# open-bldc.net
KiCad netlist of a schematic drawn in EAGLE
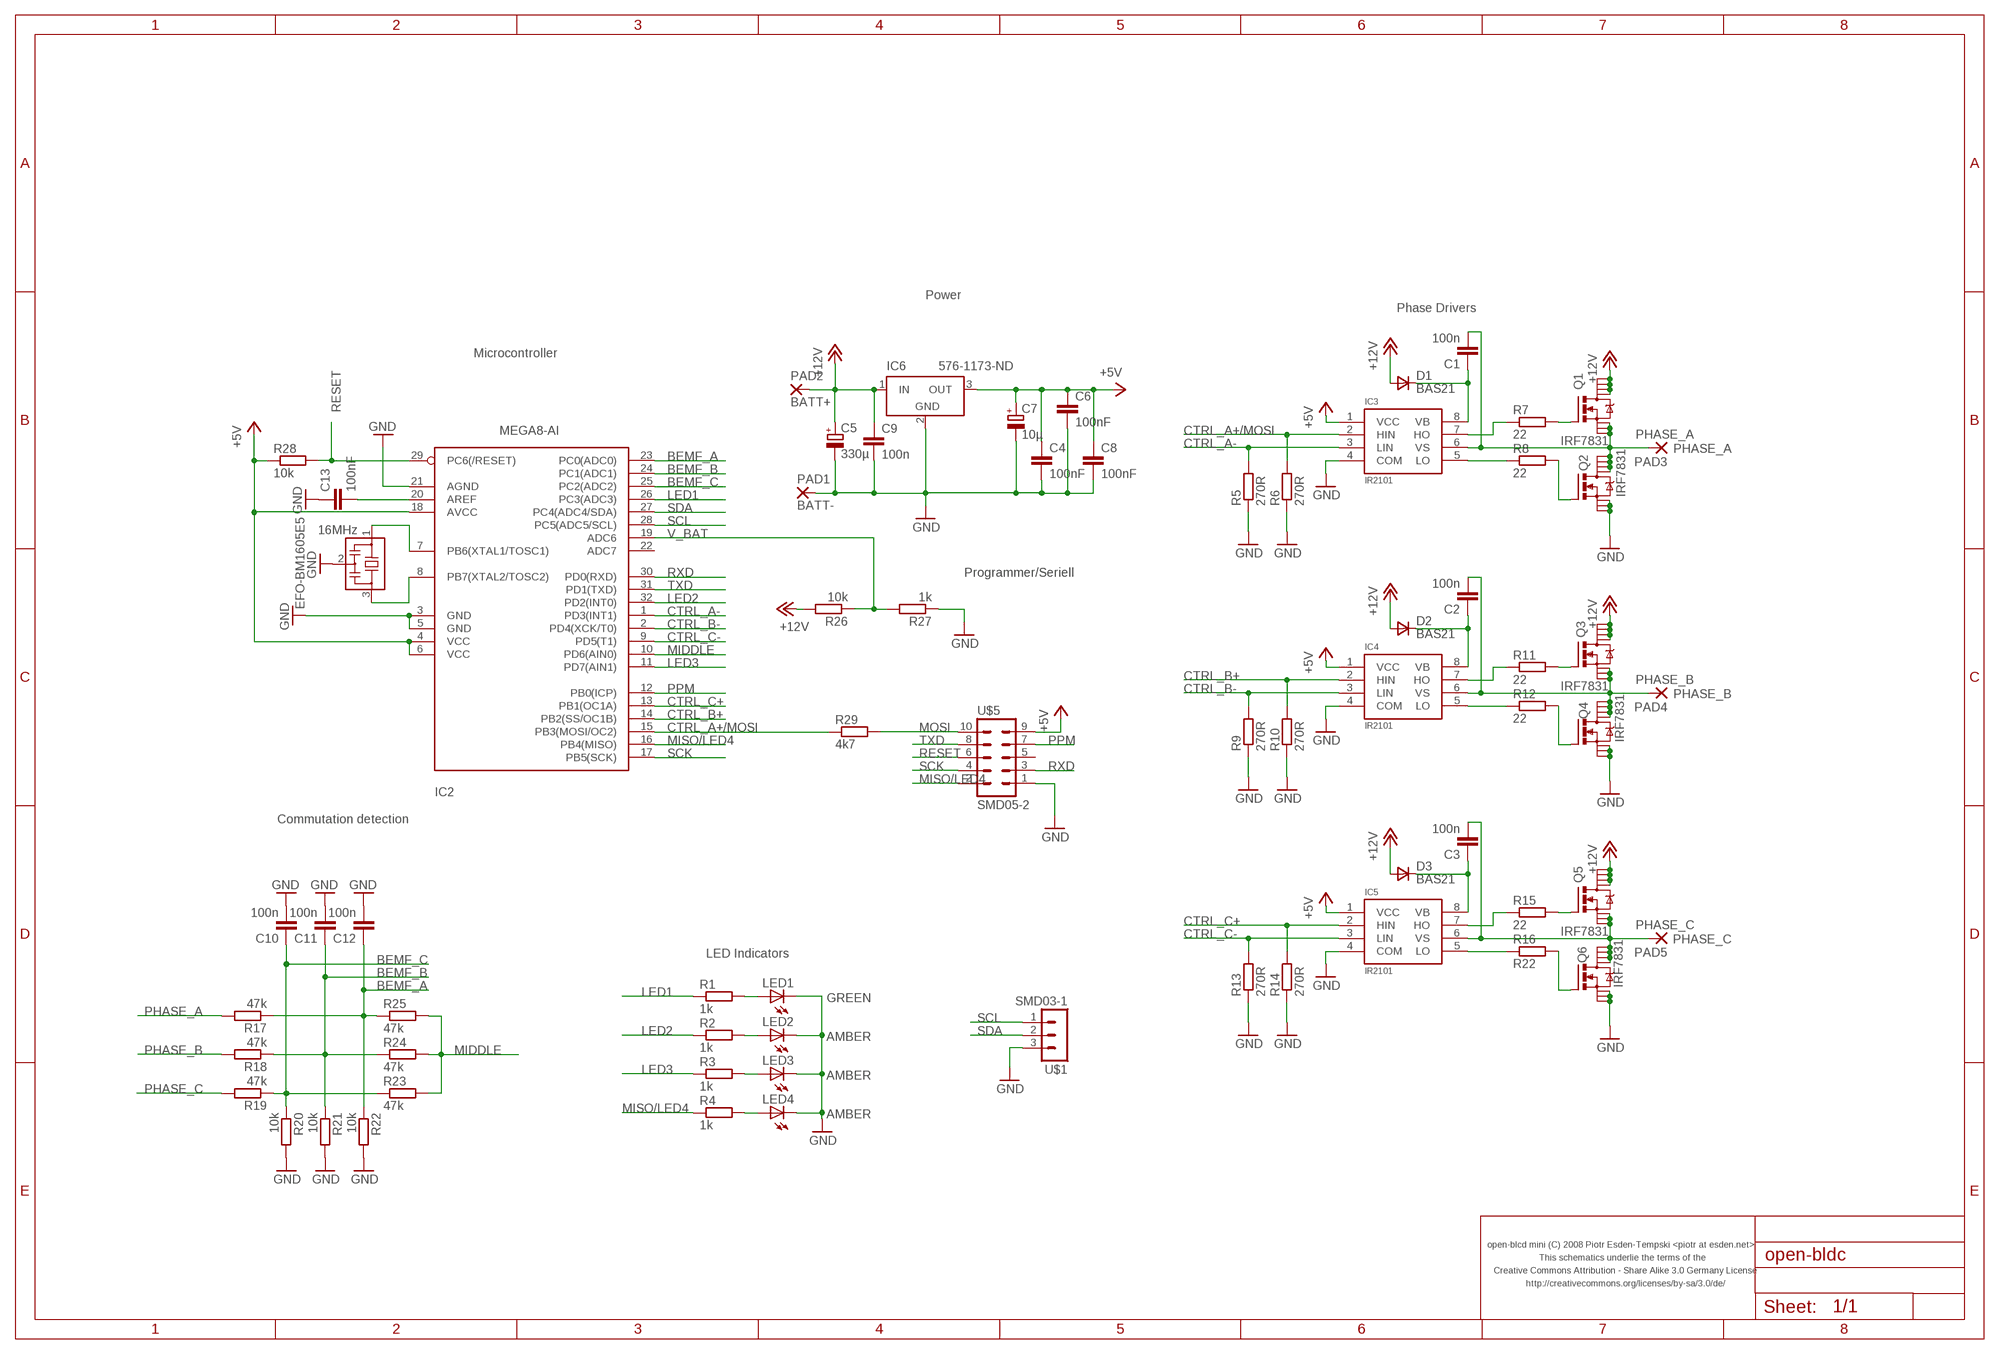
[diagram p0: schematic, sheet 1]

(export (version "E")
  (design (tool "Eeschema 10.0.6"))
  (components
    (comp (ref "C1")
      (value "100n")
      (footprint "eagle-import:C0603")
      (libsource (lib "eagle-import") (part "C-EUC0603"))
    )
    (comp (ref "C2")
      (value "100n")
      (footprint "eagle-import:C0603")
      (libsource (lib "eagle-import") (part "C-EUC0603"))
    )
    (comp (ref "C3")
      (value "100n")
      (footprint "eagle-import:C0603")
      (libsource (lib "eagle-import") (part "C-EUC0603"))
    )
    (comp (ref "C4")
      (value "100nF")
      (footprint "eagle-import:C0603")
      (libsource (lib "eagle-import") (part "C-EUC0603"))
    )
    (comp (ref "C5")
      (value "330µ")
      (footprint "eagle-import:E3,5-8")
      (libsource (lib "eagle-import") (part "CPOL-EUE3.5-8"))
    )
    (comp (ref "C6")
      (value "100nF")
      (footprint "eagle-import:C0603")
      (libsource (lib "eagle-import") (part "C-EUC0603"))
    )
    (comp (ref "C7")
      (value "10µ")
      (footprint "eagle-import:D_7343-31R")
      (libsource (lib "eagle-import") (part "CPOL-EUD/7343-31R"))
    )
    (comp (ref "C8")
      (value "100nF")
      (footprint "eagle-import:C0603")
      (libsource (lib "eagle-import") (part "C-EUC0603"))
    )
    (comp (ref "C9")
      (value "100n")
      (footprint "eagle-import:C0603")
      (libsource (lib "eagle-import") (part "C-EUC0603"))
    )
    (comp (ref "C10")
      (value "100n")
      (footprint "eagle-import:C0603")
      (libsource (lib "eagle-import") (part "C-EUC0603"))
    )
    (comp (ref "C11")
      (value "100n")
      (footprint "eagle-import:C0603")
      (libsource (lib "eagle-import") (part "C-EUC0603"))
    )
    (comp (ref "C12")
      (value "100n")
      (footprint "eagle-import:C0603")
      (libsource (lib "eagle-import") (part "C-EUC0603"))
    )
    (comp (ref "C13")
      (value "100nF")
      (footprint "eagle-import:C0603")
      (libsource (lib "eagle-import") (part "C-EUC0603"))
    )
    (comp (ref "D1")
      (value "BAS21")
      (footprint "eagle-import:SOT-23")
      (libsource (lib "eagle-import") (part "VAR2SOT23"))
    )
    (comp (ref "D2")
      (value "BAS21")
      (footprint "eagle-import:SOT-23")
      (libsource (lib "eagle-import") (part "VAR2SOT23"))
    )
    (comp (ref "D3")
      (value "BAS21")
      (footprint "eagle-import:SOT-23")
      (libsource (lib "eagle-import") (part "VAR2SOT23"))
    )
    (comp (ref "EFO-BM1605E5")
      (value "16MHz")
      (footprint "eagle-import:EFOBM")
      (libsource (lib "eagle-import") (part "EFOBM"))
    )
    (comp (ref "IC2")
      (value "MEGA8-AI")
      (footprint "eagle-import:TQFP32-08")
      (libsource (lib "eagle-import") (part "MEGA8-AI"))
    )
    (comp (ref "IC3")
      (value "IR2101")
      (footprint "eagle-import:SO-8")
      (libsource (lib "eagle-import") (part "IR2101"))
    )
    (comp (ref "IC4")
      (value "IR2101")
      (footprint "eagle-import:SO-8")
      (libsource (lib "eagle-import") (part "IR2101"))
    )
    (comp (ref "IC5")
      (value "IR2101")
      (footprint "eagle-import:SO-8")
      (libsource (lib "eagle-import") (part "IR2101"))
    )
    (comp (ref "IC6")
      (value "576-1173-ND")
      (footprint "eagle-import:SOT223")
      (libsource (lib "eagle-import") (part "LT1129CST5"))
    )
    (comp (ref "LED1")
      (value "GREEN")
      (footprint "eagle-import:CHIP-LED0603")
      (libsource (lib "eagle-import") (part "LEDCHIP-LED0603"))
    )
    (comp (ref "LED2")
      (value "AMBER")
      (footprint "eagle-import:CHIP-LED0603")
      (libsource (lib "eagle-import") (part "LEDCHIP-LED0603"))
    )
    (comp (ref "LED3")
      (value "AMBER")
      (footprint "eagle-import:CHIP-LED0603")
      (libsource (lib "eagle-import") (part "LEDCHIP-LED0603"))
    )
    (comp (ref "LED4")
      (value "AMBER")
      (footprint "eagle-import:CHIP-LED0603")
      (libsource (lib "eagle-import") (part "LEDCHIP-LED0603"))
    )
    (comp (ref "PAD1")
      (value "BATT-")
      (footprint "eagle-import:SMD2,54-5,08")
      (libsource (lib "eagle-import") (part "SMD5"))
    )
    (comp (ref "PAD2")
      (value "BATT+")
      (footprint "eagle-import:SMD2,54-5,08")
      (libsource (lib "eagle-import") (part "SMD5"))
    )
    (comp (ref "PAD3")
      (value "PHASE_A")
      (footprint "eagle-import:SMD2,54-5,08")
      (libsource (lib "eagle-import") (part "SMD5"))
    )
    (comp (ref "PAD4")
      (value "PHASE_B")
      (footprint "eagle-import:SMD2,54-5,08")
      (libsource (lib "eagle-import") (part "SMD5"))
    )
    (comp (ref "PAD5")
      (value "PHASE_C")
      (footprint "eagle-import:SMD2,54-5,08")
      (libsource (lib "eagle-import") (part "SMD5"))
    )
    (comp (ref "Q1")
      (value "IRF7831")
      (footprint "eagle-import:SO-08")
      (libsource (lib "eagle-import") (part "N-MOSFET-SO8S"))
    )
    (comp (ref "Q2")
      (value "IRF7831")
      (footprint "eagle-import:SO-08")
      (libsource (lib "eagle-import") (part "N-MOSFET-SO8S"))
    )
    (comp (ref "Q3")
      (value "IRF7831")
      (footprint "eagle-import:SO-08")
      (libsource (lib "eagle-import") (part "N-MOSFET-SO8S"))
    )
    (comp (ref "Q4")
      (value "IRF7831")
      (footprint "eagle-import:SO-08")
      (libsource (lib "eagle-import") (part "N-MOSFET-SO8S"))
    )
    (comp (ref "Q5")
      (value "IRF7831")
      (footprint "eagle-import:SO-08")
      (libsource (lib "eagle-import") (part "N-MOSFET-SO8S"))
    )
    (comp (ref "Q6")
      (value "IRF7831")
      (footprint "eagle-import:SO-08")
      (libsource (lib "eagle-import") (part "N-MOSFET-SO8S"))
    )
    (comp (ref "R1")
      (value "1k")
      (footprint "eagle-import:R0603")
      (libsource (lib "eagle-import") (part "R-EU_R0603"))
    )
    (comp (ref "R2")
      (value "1k")
      (footprint "eagle-import:R0603")
      (libsource (lib "eagle-import") (part "R-EU_R0603"))
    )
    (comp (ref "R3")
      (value "1k")
      (footprint "eagle-import:R0603")
      (libsource (lib "eagle-import") (part "R-EU_R0603"))
    )
    (comp (ref "R4")
      (value "1k")
      (footprint "eagle-import:R0603")
      (libsource (lib "eagle-import") (part "R-EU_R0603"))
    )
    (comp (ref "R5")
      (value "270R")
      (footprint "eagle-import:R0603")
      (libsource (lib "eagle-import") (part "R-EU_R0603"))
    )
    (comp (ref "R6")
      (value "270R")
      (footprint "eagle-import:R0603")
      (libsource (lib "eagle-import") (part "R-EU_R0603"))
    )
    (comp (ref "R7")
      (value "22")
      (footprint "eagle-import:R0603")
      (libsource (lib "eagle-import") (part "R-EU_R0603"))
    )
    (comp (ref "R8")
      (value "22")
      (footprint "eagle-import:R0603")
      (libsource (lib "eagle-import") (part "R-EU_R0603"))
    )
    (comp (ref "R9")
      (value "270R")
      (footprint "eagle-import:R0603")
      (libsource (lib "eagle-import") (part "R-EU_R0603"))
    )
    (comp (ref "R10")
      (value "270R")
      (footprint "eagle-import:R0603")
      (libsource (lib "eagle-import") (part "R-EU_R0603"))
    )
    (comp (ref "R11")
      (value "22")
      (footprint "eagle-import:R0603")
      (libsource (lib "eagle-import") (part "R-EU_R0603"))
    )
    (comp (ref "R12")
      (value "22")
      (footprint "eagle-import:R0603")
      (libsource (lib "eagle-import") (part "R-EU_R0603"))
    )
    (comp (ref "R13")
      (value "270R")
      (footprint "eagle-import:R0603")
      (libsource (lib "eagle-import") (part "R-EU_R0603"))
    )
    (comp (ref "R14")
      (value "270R")
      (footprint "eagle-import:R0603")
      (libsource (lib "eagle-import") (part "R-EU_R0603"))
    )
    (comp (ref "R15")
      (value "22")
      (footprint "eagle-import:R0603")
      (libsource (lib "eagle-import") (part "R-EU_R0603"))
    )
    (comp (ref "R16")
      (value "R22")
      (footprint "eagle-import:R0603")
      (libsource (lib "eagle-import") (part "R-EU_R0603"))
    )
    (comp (ref "R17")
      (value "47k")
      (footprint "eagle-import:R0603")
      (libsource (lib "eagle-import") (part "R-EU_R0603"))
    )
    (comp (ref "R18")
      (value "47k")
      (footprint "eagle-import:R0603")
      (libsource (lib "eagle-import") (part "R-EU_R0603"))
    )
    (comp (ref "R19")
      (value "47k")
      (footprint "eagle-import:R0603")
      (libsource (lib "eagle-import") (part "R-EU_R0603"))
    )
    (comp (ref "R20")
      (value "10k")
      (footprint "eagle-import:R0603")
      (libsource (lib "eagle-import") (part "R-EU_R0603"))
    )
    (comp (ref "R21")
      (value "10k")
      (footprint "eagle-import:R0603")
      (libsource (lib "eagle-import") (part "R-EU_R0603"))
    )
    (comp (ref "R22")
      (value "10k")
      (footprint "eagle-import:R0603")
      (libsource (lib "eagle-import") (part "R-EU_R0603"))
    )
    (comp (ref "R23")
      (value "47k")
      (footprint "eagle-import:R0603")
      (libsource (lib "eagle-import") (part "R-EU_R0603"))
    )
    (comp (ref "R24")
      (value "47k")
      (footprint "eagle-import:R0603")
      (libsource (lib "eagle-import") (part "R-EU_R0603"))
    )
    (comp (ref "R25")
      (value "47k")
      (footprint "eagle-import:R0603")
      (libsource (lib "eagle-import") (part "R-EU_R0603"))
    )
    (comp (ref "R26")
      (value "10k")
      (footprint "eagle-import:R0603")
      (libsource (lib "eagle-import") (part "R-EU_R0603"))
    )
    (comp (ref "R27")
      (value "1k")
      (footprint "eagle-import:R0603")
      (libsource (lib "eagle-import") (part "R-EU_R0603"))
    )
    (comp (ref "R28")
      (value "10k")
      (footprint "eagle-import:R0603")
      (libsource (lib "eagle-import") (part "R-EU_R0603"))
    )
    (comp (ref "R29")
      (value "4k7")
      (footprint "eagle-import:R0603")
      (libsource (lib "eagle-import") (part "R-EU_R0603"))
    )
    (comp (ref "U$1")
      (value "SMD03-1")
      (footprint "eagle-import:SMD03-1")
      (libsource (lib "eagle-import") (part "SMD03-1"))
    )
    (comp (ref "U$5")
      (value "SMD05-2")
      (footprint "eagle-import:SMD05-2")
      (libsource (lib "eagle-import") (part "SMD05-2"))
    )
  )
  (nets
    (net (code "1") (name "+5V") (class "Default")
      (node (ref "C4") (pin "1") (pinfunction "1_1") (pintype "passive"))
      (node (ref "C6") (pin "1") (pinfunction "1_1") (pintype "passive"))
      (node (ref "C7") (pin "+") (pinfunction "+_+") (pintype "passive"))
      (node (ref "C8") (pin "1") (pinfunction "1_1") (pintype "passive"))
      (node (ref "IC2") (pin "18") (pinfunction "AVCC_18") (pintype "power_in"))
      (node (ref "IC2") (pin "4") (pinfunction "VCC_4") (pintype "power_in"))
      (node (ref "IC2") (pin "6") (pinfunction "VCC_6") (pintype "power_in"))
      (node (ref "IC3") (pin "1") (pinfunction "VCC_1") (pintype "bidirectional"))
      (node (ref "IC4") (pin "1") (pinfunction "VCC_1") (pintype "bidirectional"))
      (node (ref "IC5") (pin "1") (pinfunction "VCC_1") (pintype "bidirectional"))
      (node (ref "IC6") (pin "3") (pinfunction "OUT_3") (pintype "output"))
      (node (ref "R28") (pin "1") (pinfunction "1_1") (pintype "passive"))
      (node (ref "U$5") (pin "9") (pinfunction "9_9") (pintype "passive"))
    )
    (net (code "2") (name "+12V") (class "Default")
      (node (ref "C5") (pin "+") (pinfunction "+_+") (pintype "passive"))
      (node (ref "C9") (pin "1") (pinfunction "1_1") (pintype "passive"))
      (node (ref "D1") (pin "3") (pinfunction "A_3") (pintype "passive"))
      (node (ref "D2") (pin "3") (pinfunction "A_3") (pintype "passive"))
      (node (ref "D3") (pin "3") (pinfunction "A_3") (pintype "passive"))
      (node (ref "IC6") (pin "1") (pinfunction "IN_1") (pintype "input"))
      (node (ref "PAD2") (pin "1") (pinfunction "P_1") (pintype "passive"))
      (node (ref "Q1") (pin "5") (pinfunction "D_5") (pintype "passive"))
      (node (ref "Q1") (pin "6") (pinfunction "D_6") (pintype "passive"))
      (node (ref "Q1") (pin "7") (pinfunction "D_7") (pintype "passive"))
      (node (ref "Q1") (pin "8") (pinfunction "D_8") (pintype "passive"))
      (node (ref "Q3") (pin "5") (pinfunction "D_5") (pintype "passive"))
      (node (ref "Q3") (pin "6") (pinfunction "D_6") (pintype "passive"))
      (node (ref "Q3") (pin "7") (pinfunction "D_7") (pintype "passive"))
      (node (ref "Q3") (pin "8") (pinfunction "D_8") (pintype "passive"))
      (node (ref "Q5") (pin "5") (pinfunction "D_5") (pintype "passive"))
      (node (ref "Q5") (pin "6") (pinfunction "D_6") (pintype "passive"))
      (node (ref "Q5") (pin "7") (pinfunction "D_7") (pintype "passive"))
      (node (ref "Q5") (pin "8") (pinfunction "D_8") (pintype "passive"))
      (node (ref "R26") (pin "2") (pinfunction "2_2") (pintype "passive"))
    )
    (net (code "3") (name "/BEMF_A") (class "Default")
      (node (ref "C12") (pin "1") (pinfunction "1_1") (pintype "passive"))
      (node (ref "IC2") (pin "23") (pinfunction "PC0(ADC0)_23") (pintype "bidirectional"))
      (node (ref "R17") (pin "1") (pinfunction "1_1") (pintype "passive"))
      (node (ref "R22") (pin "1") (pinfunction "1_1") (pintype "passive"))
      (node (ref "R25") (pin "1") (pinfunction "1_1") (pintype "passive"))
    )
    (net (code "4") (name "/BEMF_B") (class "Default")
      (node (ref "C11") (pin "1") (pinfunction "1_1") (pintype "passive"))
      (node (ref "IC2") (pin "24") (pinfunction "PC1(ADC1)_24") (pintype "bidirectional"))
      (node (ref "R18") (pin "1") (pinfunction "1_1") (pintype "passive"))
      (node (ref "R21") (pin "1") (pinfunction "1_1") (pintype "passive"))
      (node (ref "R24") (pin "1") (pinfunction "1_1") (pintype "passive"))
    )
    (net (code "5") (name "/BEMF_C") (class "Default")
      (node (ref "C10") (pin "1") (pinfunction "1_1") (pintype "passive"))
      (node (ref "IC2") (pin "25") (pinfunction "PC2(ADC2)_25") (pintype "bidirectional"))
      (node (ref "R19") (pin "1") (pinfunction "1_1") (pintype "passive"))
      (node (ref "R20") (pin "1") (pinfunction "1_1") (pintype "passive"))
      (node (ref "R23") (pin "1") (pinfunction "1_1") (pintype "passive"))
    )
    (net (code "6") (name "/CTRL_A+{slash}MOSI") (class "Default")
      (node (ref "IC2") (pin "15") (pinfunction "PB3(MOSI/OC2)_15") (pintype "bidirectional"))
      (node (ref "IC3") (pin "2") (pinfunction "HIN_2") (pintype "bidirectional"))
      (node (ref "R29") (pin "1") (pinfunction "1_1") (pintype "passive"))
      (node (ref "R6") (pin "2") (pinfunction "2_2") (pintype "passive"))
    )
    (net (code "7") (name "/CTRL_A-") (class "Default")
      (node (ref "IC2") (pin "1") (pinfunction "PD3(INT1)_1") (pintype "bidirectional"))
      (node (ref "IC3") (pin "3") (pinfunction "LIN_3") (pintype "bidirectional"))
      (node (ref "R5") (pin "2") (pinfunction "2_2") (pintype "passive"))
    )
    (net (code "8") (name "/CTRL_B+") (class "Default")
      (node (ref "IC2") (pin "14") (pinfunction "PB2(SS/OC1B)_14") (pintype "bidirectional"))
      (node (ref "IC4") (pin "2") (pinfunction "HIN_2") (pintype "bidirectional"))
      (node (ref "R10") (pin "2") (pinfunction "2_2") (pintype "passive"))
    )
    (net (code "9") (name "/CTRL_B-") (class "Default")
      (node (ref "IC2") (pin "2") (pinfunction "PD4(XCK/T0)_2") (pintype "bidirectional"))
      (node (ref "IC4") (pin "3") (pinfunction "LIN_3") (pintype "bidirectional"))
      (node (ref "R9") (pin "2") (pinfunction "2_2") (pintype "passive"))
    )
    (net (code "10") (name "/CTRL_C+") (class "Default")
      (node (ref "IC2") (pin "13") (pinfunction "PB1(OC1A)_13") (pintype "bidirectional"))
      (node (ref "IC5") (pin "2") (pinfunction "HIN_2") (pintype "bidirectional"))
      (node (ref "R14") (pin "2") (pinfunction "2_2") (pintype "passive"))
    )
    (net (code "11") (name "/CTRL_C-") (class "Default")
      (node (ref "IC2") (pin "9") (pinfunction "PD5(T1)_9") (pintype "bidirectional"))
      (node (ref "IC5") (pin "3") (pinfunction "LIN_3") (pintype "bidirectional"))
      (node (ref "R13") (pin "2") (pinfunction "2_2") (pintype "passive"))
    )
    (net (code "12") (name "/LED1") (class "Default")
      (node (ref "IC2") (pin "26") (pinfunction "PC3(ADC3)_26") (pintype "bidirectional"))
      (node (ref "R1") (pin "1") (pinfunction "1_1") (pintype "passive"))
    )
    (net (code "13") (name "/LED2") (class "Default")
      (node (ref "IC2") (pin "32") (pinfunction "PD2(INT0)_32") (pintype "bidirectional"))
      (node (ref "R2") (pin "1") (pinfunction "1_1") (pintype "passive"))
    )
    (net (code "14") (name "/LED3") (class "Default")
      (node (ref "IC2") (pin "11") (pinfunction "PD7(AIN1)_11") (pintype "bidirectional"))
      (node (ref "R3") (pin "1") (pinfunction "1_1") (pintype "passive"))
    )
    (net (code "15") (name "/MIDDLE") (class "Default")
      (node (ref "IC2") (pin "10") (pinfunction "PD6(AIN0)_10") (pintype "bidirectional"))
      (node (ref "R23") (pin "2") (pinfunction "2_2") (pintype "passive"))
      (node (ref "R24") (pin "2") (pinfunction "2_2") (pintype "passive"))
      (node (ref "R25") (pin "2") (pinfunction "2_2") (pintype "passive"))
    )
    (net (code "16") (name "/MISO{slash}LED4") (class "Default")
      (node (ref "IC2") (pin "16") (pinfunction "PB4(MISO)_16") (pintype "bidirectional"))
      (node (ref "R4") (pin "1") (pinfunction "1_1") (pintype "passive"))
      (node (ref "U$5") (pin "2") (pinfunction "2_2") (pintype "passive"))
    )
    (net (code "17") (name "/MOSI") (class "Default")
      (node (ref "R29") (pin "2") (pinfunction "2_2") (pintype "passive"))
      (node (ref "U$5") (pin "10") (pinfunction "10_10") (pintype "passive"))
    )
    (net (code "18") (name "/PHASE_A") (class "Default")
      (node (ref "C1") (pin "2") (pinfunction "2_2") (pintype "passive"))
      (node (ref "IC3") (pin "6") (pinfunction "VS_6") (pintype "bidirectional"))
      (node (ref "PAD3") (pin "1") (pinfunction "P_1") (pintype "passive"))
      (node (ref "Q1") (pin "1") (pinfunction "S_1") (pintype "passive"))
      (node (ref "Q1") (pin "2") (pinfunction "S_2") (pintype "passive"))
      (node (ref "Q1") (pin "3") (pinfunction "S_3") (pintype "passive"))
      (node (ref "Q2") (pin "5") (pinfunction "D_5") (pintype "passive"))
      (node (ref "Q2") (pin "6") (pinfunction "D_6") (pintype "passive"))
      (node (ref "Q2") (pin "7") (pinfunction "D_7") (pintype "passive"))
      (node (ref "Q2") (pin "8") (pinfunction "D_8") (pintype "passive"))
      (node (ref "R17") (pin "2") (pinfunction "2_2") (pintype "passive"))
    )
    (net (code "19") (name "/PHASE_B") (class "Default")
      (node (ref "C2") (pin "2") (pinfunction "2_2") (pintype "passive"))
      (node (ref "IC4") (pin "6") (pinfunction "VS_6") (pintype "bidirectional"))
      (node (ref "PAD4") (pin "1") (pinfunction "P_1") (pintype "passive"))
      (node (ref "Q3") (pin "1") (pinfunction "S_1") (pintype "passive"))
      (node (ref "Q3") (pin "2") (pinfunction "S_2") (pintype "passive"))
      (node (ref "Q3") (pin "3") (pinfunction "S_3") (pintype "passive"))
      (node (ref "Q4") (pin "5") (pinfunction "D_5") (pintype "passive"))
      (node (ref "Q4") (pin "6") (pinfunction "D_6") (pintype "passive"))
      (node (ref "Q4") (pin "7") (pinfunction "D_7") (pintype "passive"))
      (node (ref "Q4") (pin "8") (pinfunction "D_8") (pintype "passive"))
      (node (ref "R18") (pin "2") (pinfunction "2_2") (pintype "passive"))
    )
    (net (code "20") (name "/PHASE_C") (class "Default")
      (node (ref "C3") (pin "2") (pinfunction "2_2") (pintype "passive"))
      (node (ref "IC5") (pin "6") (pinfunction "VS_6") (pintype "bidirectional"))
      (node (ref "PAD5") (pin "1") (pinfunction "P_1") (pintype "passive"))
      (node (ref "Q5") (pin "1") (pinfunction "S_1") (pintype "passive"))
      (node (ref "Q5") (pin "2") (pinfunction "S_2") (pintype "passive"))
      (node (ref "Q5") (pin "3") (pinfunction "S_3") (pintype "passive"))
      (node (ref "Q6") (pin "5") (pinfunction "D_5") (pintype "passive"))
      (node (ref "Q6") (pin "6") (pinfunction "D_6") (pintype "passive"))
      (node (ref "Q6") (pin "7") (pinfunction "D_7") (pintype "passive"))
      (node (ref "Q6") (pin "8") (pinfunction "D_8") (pintype "passive"))
      (node (ref "R19") (pin "2") (pinfunction "2_2") (pintype "passive"))
    )
    (net (code "21") (name "/PPM") (class "Default")
      (node (ref "IC2") (pin "12") (pinfunction "PB0(ICP)_12") (pintype "bidirectional"))
      (node (ref "U$5") (pin "7") (pinfunction "7_7") (pintype "passive"))
    )
    (net (code "22") (name "/RESET") (class "Default")
      (node (ref "IC2") (pin "29") (pinfunction "PC6(/RESET)_29") (pintype "bidirectional"))
      (node (ref "R28") (pin "2") (pinfunction "2_2") (pintype "passive"))
      (node (ref "U$5") (pin "6") (pinfunction "6_6") (pintype "passive"))
    )
    (net (code "23") (name "/RXD") (class "Default")
      (node (ref "IC2") (pin "30") (pinfunction "PD0(RXD)_30") (pintype "bidirectional"))
      (node (ref "U$5") (pin "3") (pinfunction "3_3") (pintype "passive"))
    )
    (net (code "24") (name "/SCK") (class "Default")
      (node (ref "IC2") (pin "17") (pinfunction "PB5(SCK)_17") (pintype "bidirectional"))
      (node (ref "U$5") (pin "4") (pinfunction "4_4") (pintype "passive"))
    )
    (net (code "25") (name "/SCL") (class "Default")
      (node (ref "IC2") (pin "28") (pinfunction "PC5(ADC5/SCL)_28") (pintype "bidirectional"))
      (node (ref "U$1") (pin "1") (pinfunction "1_1") (pintype "passive"))
    )
    (net (code "26") (name "/SDA") (class "Default")
      (node (ref "IC2") (pin "27") (pinfunction "PC4(ADC4/SDA)_27") (pintype "bidirectional"))
      (node (ref "U$1") (pin "2") (pinfunction "2_2") (pintype "passive"))
    )
    (net (code "27") (name "/TXD") (class "Default")
      (node (ref "IC2") (pin "31") (pinfunction "PD1(TXD)_31") (pintype "bidirectional"))
      (node (ref "U$5") (pin "8") (pinfunction "8_8") (pintype "passive"))
    )
    (net (code "28") (name "/V_BAT") (class "Default")
      (node (ref "IC2") (pin "19") (pinfunction "ADC6_19") (pintype "bidirectional"))
      (node (ref "R26") (pin "1") (pinfunction "1_1") (pintype "passive"))
      (node (ref "R27") (pin "2") (pinfunction "2_2") (pintype "passive"))
    )
    (net (code "29") (name "GND") (class "Default")
      (node (ref "C10") (pin "2") (pinfunction "2_2") (pintype "passive"))
      (node (ref "C11") (pin "2") (pinfunction "2_2") (pintype "passive"))
      (node (ref "C12") (pin "2") (pinfunction "2_2") (pintype "passive"))
      (node (ref "C13") (pin "1") (pinfunction "1_1") (pintype "passive"))
      (node (ref "C4") (pin "2") (pinfunction "2_2") (pintype "passive"))
      (node (ref "C5") (pin "-") (pinfunction "-_-") (pintype "passive"))
      (node (ref "C6") (pin "2") (pinfunction "2_2") (pintype "passive"))
      (node (ref "C7") (pin "-") (pinfunction "-_-") (pintype "passive"))
      (node (ref "C8") (pin "2") (pinfunction "2_2") (pintype "passive"))
      (node (ref "C9") (pin "2") (pinfunction "2_2") (pintype "passive"))
      (node (ref "EFO-BM1605E5") (pin "2") (pinfunction "2_2") (pintype "passive"))
      (node (ref "IC2") (pin "21") (pinfunction "AGND_21") (pintype "power_in"))
      (node (ref "IC2") (pin "3") (pinfunction "GND_3") (pintype "power_in"))
      (node (ref "IC2") (pin "5") (pinfunction "GND_5") (pintype "power_in"))
      (node (ref "IC3") (pin "4") (pinfunction "COM_4") (pintype "bidirectional"))
      (node (ref "IC4") (pin "4") (pinfunction "COM_4") (pintype "bidirectional"))
      (node (ref "IC5") (pin "4") (pinfunction "COM_4") (pintype "bidirectional"))
      (node (ref "IC6") (pin "2") (pinfunction "GND_2") (pintype "power_in"))
      (node (ref "LED1") (pin "C") (pinfunction "C_C") (pintype "passive"))
      (node (ref "LED2") (pin "C") (pinfunction "C_C") (pintype "passive"))
      (node (ref "LED3") (pin "C") (pinfunction "C_C") (pintype "passive"))
      (node (ref "LED4") (pin "C") (pinfunction "C_C") (pintype "passive"))
      (node (ref "PAD1") (pin "1") (pinfunction "P_1") (pintype "passive"))
      (node (ref "Q2") (pin "1") (pinfunction "S_1") (pintype "passive"))
      (node (ref "Q2") (pin "2") (pinfunction "S_2") (pintype "passive"))
      (node (ref "Q2") (pin "3") (pinfunction "S_3") (pintype "passive"))
      (node (ref "Q4") (pin "1") (pinfunction "S_1") (pintype "passive"))
      (node (ref "Q4") (pin "2") (pinfunction "S_2") (pintype "passive"))
      (node (ref "Q4") (pin "3") (pinfunction "S_3") (pintype "passive"))
      (node (ref "Q6") (pin "1") (pinfunction "S_1") (pintype "passive"))
      (node (ref "Q6") (pin "2") (pinfunction "S_2") (pintype "passive"))
      (node (ref "Q6") (pin "3") (pinfunction "S_3") (pintype "passive"))
      (node (ref "R10") (pin "1") (pinfunction "1_1") (pintype "passive"))
      (node (ref "R13") (pin "1") (pinfunction "1_1") (pintype "passive"))
      (node (ref "R14") (pin "1") (pinfunction "1_1") (pintype "passive"))
      (node (ref "R20") (pin "2") (pinfunction "2_2") (pintype "passive"))
      (node (ref "R21") (pin "2") (pinfunction "2_2") (pintype "passive"))
      (node (ref "R22") (pin "2") (pinfunction "2_2") (pintype "passive"))
      (node (ref "R27") (pin "1") (pinfunction "1_1") (pintype "passive"))
      (node (ref "R5") (pin "1") (pinfunction "1_1") (pintype "passive"))
      (node (ref "R6") (pin "1") (pinfunction "1_1") (pintype "passive"))
      (node (ref "R9") (pin "1") (pinfunction "1_1") (pintype "passive"))
      (node (ref "U$1") (pin "3") (pinfunction "3_3") (pintype "passive"))
      (node (ref "U$5") (pin "1") (pinfunction "1_1") (pintype "passive"))
    )
    (net (code "30") (name "Net-(D1-C)") (class "Default")
      (node (ref "C1") (pin "1") (pinfunction "1_1") (pintype "passive"))
      (node (ref "D1") (pin "1") (pinfunction "C_1") (pintype "passive"))
      (node (ref "IC3") (pin "8") (pinfunction "VB_8") (pintype "bidirectional"))
    )
    (net (code "31") (name "Net-(D2-C)") (class "Default")
      (node (ref "C2") (pin "1") (pinfunction "1_1") (pintype "passive"))
      (node (ref "D2") (pin "1") (pinfunction "C_1") (pintype "passive"))
      (node (ref "IC4") (pin "8") (pinfunction "VB_8") (pintype "bidirectional"))
    )
    (net (code "32") (name "Net-(D3-C)") (class "Default")
      (node (ref "C3") (pin "1") (pinfunction "1_1") (pintype "passive"))
      (node (ref "D3") (pin "1") (pinfunction "C_1") (pintype "passive"))
      (node (ref "IC5") (pin "8") (pinfunction "VB_8") (pintype "bidirectional"))
    )
    (net (code "33") (name "Net-(IC2-AREF)") (class "Default")
      (node (ref "C13") (pin "2") (pinfunction "2_2") (pintype "passive"))
      (node (ref "IC2") (pin "20") (pinfunction "AREF_20") (pintype "passive"))
    )
    (net (code "34") (name "Net-(IC2-PB6(XTAL1{slash}TOSC1))") (class "Default")
      (node (ref "EFO-BM1605E5") (pin "1") (pinfunction "1_1") (pintype "passive"))
      (node (ref "IC2") (pin "7") (pinfunction "PB6(XTAL1/TOSC1)_7") (pintype "bidirectional"))
    )
    (net (code "35") (name "Net-(IC2-PB7(XTAL2{slash}TOSC2))") (class "Default")
      (node (ref "EFO-BM1605E5") (pin "3") (pinfunction "3_3") (pintype "passive"))
      (node (ref "IC2") (pin "8") (pinfunction "PB7(XTAL2/TOSC2)_8") (pintype "bidirectional"))
    )
    (net (code "36") (name "Net-(IC3-HO)") (class "Default")
      (node (ref "IC3") (pin "7") (pinfunction "HO_7") (pintype "bidirectional"))
      (node (ref "R7") (pin "1") (pinfunction "1_1") (pintype "passive"))
    )
    (net (code "37") (name "Net-(IC3-LO)") (class "Default")
      (node (ref "IC3") (pin "5") (pinfunction "LO_5") (pintype "bidirectional"))
      (node (ref "R8") (pin "1") (pinfunction "1_1") (pintype "passive"))
    )
    (net (code "38") (name "Net-(IC4-HO)") (class "Default")
      (node (ref "IC4") (pin "7") (pinfunction "HO_7") (pintype "bidirectional"))
      (node (ref "R11") (pin "1") (pinfunction "1_1") (pintype "passive"))
    )
    (net (code "39") (name "Net-(IC4-LO)") (class "Default")
      (node (ref "IC4") (pin "5") (pinfunction "LO_5") (pintype "bidirectional"))
      (node (ref "R12") (pin "1") (pinfunction "1_1") (pintype "passive"))
    )
    (net (code "40") (name "Net-(IC5-HO)") (class "Default")
      (node (ref "IC5") (pin "7") (pinfunction "HO_7") (pintype "bidirectional"))
      (node (ref "R15") (pin "1") (pinfunction "1_1") (pintype "passive"))
    )
    (net (code "41") (name "Net-(IC5-LO)") (class "Default")
      (node (ref "IC5") (pin "5") (pinfunction "LO_5") (pintype "bidirectional"))
      (node (ref "R16") (pin "1") (pinfunction "1_1") (pintype "passive"))
    )
    (net (code "42") (name "Net-(LED1-PadA)") (class "Default")
      (node (ref "LED1") (pin "A") (pinfunction "A_A") (pintype "passive"))
      (node (ref "R1") (pin "2") (pinfunction "2_2") (pintype "passive"))
    )
    (net (code "43") (name "Net-(LED2-PadA)") (class "Default")
      (node (ref "LED2") (pin "A") (pinfunction "A_A") (pintype "passive"))
      (node (ref "R2") (pin "2") (pinfunction "2_2") (pintype "passive"))
    )
    (net (code "44") (name "Net-(LED3-PadA)") (class "Default")
      (node (ref "LED3") (pin "A") (pinfunction "A_A") (pintype "passive"))
      (node (ref "R3") (pin "2") (pinfunction "2_2") (pintype "passive"))
    )
    (net (code "45") (name "Net-(LED4-PadA)") (class "Default")
      (node (ref "LED4") (pin "A") (pinfunction "A_A") (pintype "passive"))
      (node (ref "R4") (pin "2") (pinfunction "2_2") (pintype "passive"))
    )
    (net (code "46") (name "Net-(Q1-G)") (class "Default")
      (node (ref "Q1") (pin "4") (pinfunction "G_4") (pintype "passive"))
      (node (ref "R7") (pin "2") (pinfunction "2_2") (pintype "passive"))
    )
    (net (code "47") (name "Net-(Q2-G)") (class "Default")
      (node (ref "Q2") (pin "4") (pinfunction "G_4") (pintype "passive"))
      (node (ref "R8") (pin "2") (pinfunction "2_2") (pintype "passive"))
    )
    (net (code "48") (name "Net-(Q3-G)") (class "Default")
      (node (ref "Q3") (pin "4") (pinfunction "G_4") (pintype "passive"))
      (node (ref "R11") (pin "2") (pinfunction "2_2") (pintype "passive"))
    )
    (net (code "49") (name "Net-(Q4-G)") (class "Default")
      (node (ref "Q4") (pin "4") (pinfunction "G_4") (pintype "passive"))
      (node (ref "R12") (pin "2") (pinfunction "2_2") (pintype "passive"))
    )
    (net (code "50") (name "Net-(Q5-G)") (class "Default")
      (node (ref "Q5") (pin "4") (pinfunction "G_4") (pintype "passive"))
      (node (ref "R15") (pin "2") (pinfunction "2_2") (pintype "passive"))
    )
    (net (code "51") (name "Net-(Q6-G)") (class "Default")
      (node (ref "Q6") (pin "4") (pinfunction "G_4") (pintype "passive"))
      (node (ref "R16") (pin "2") (pinfunction "2_2") (pintype "passive"))
    )
    (net (code "52") (name "unconnected-(IC2-ADC7-Pad22)") (class "Default")
      (node (ref "IC2") (pin "22") (pinfunction "ADC7_22") (pintype "bidirectional"))
    )
    (net (code "53") (name "unconnected-(U$5-Pad5)") (class "Default")
      (node (ref "U$5") (pin "5") (pinfunction "5_5") (pintype "passive"))
    )
  )
)
